# Blank_48LQFP_header.net
KiCad netlist of a schematic drawn in EAGLE
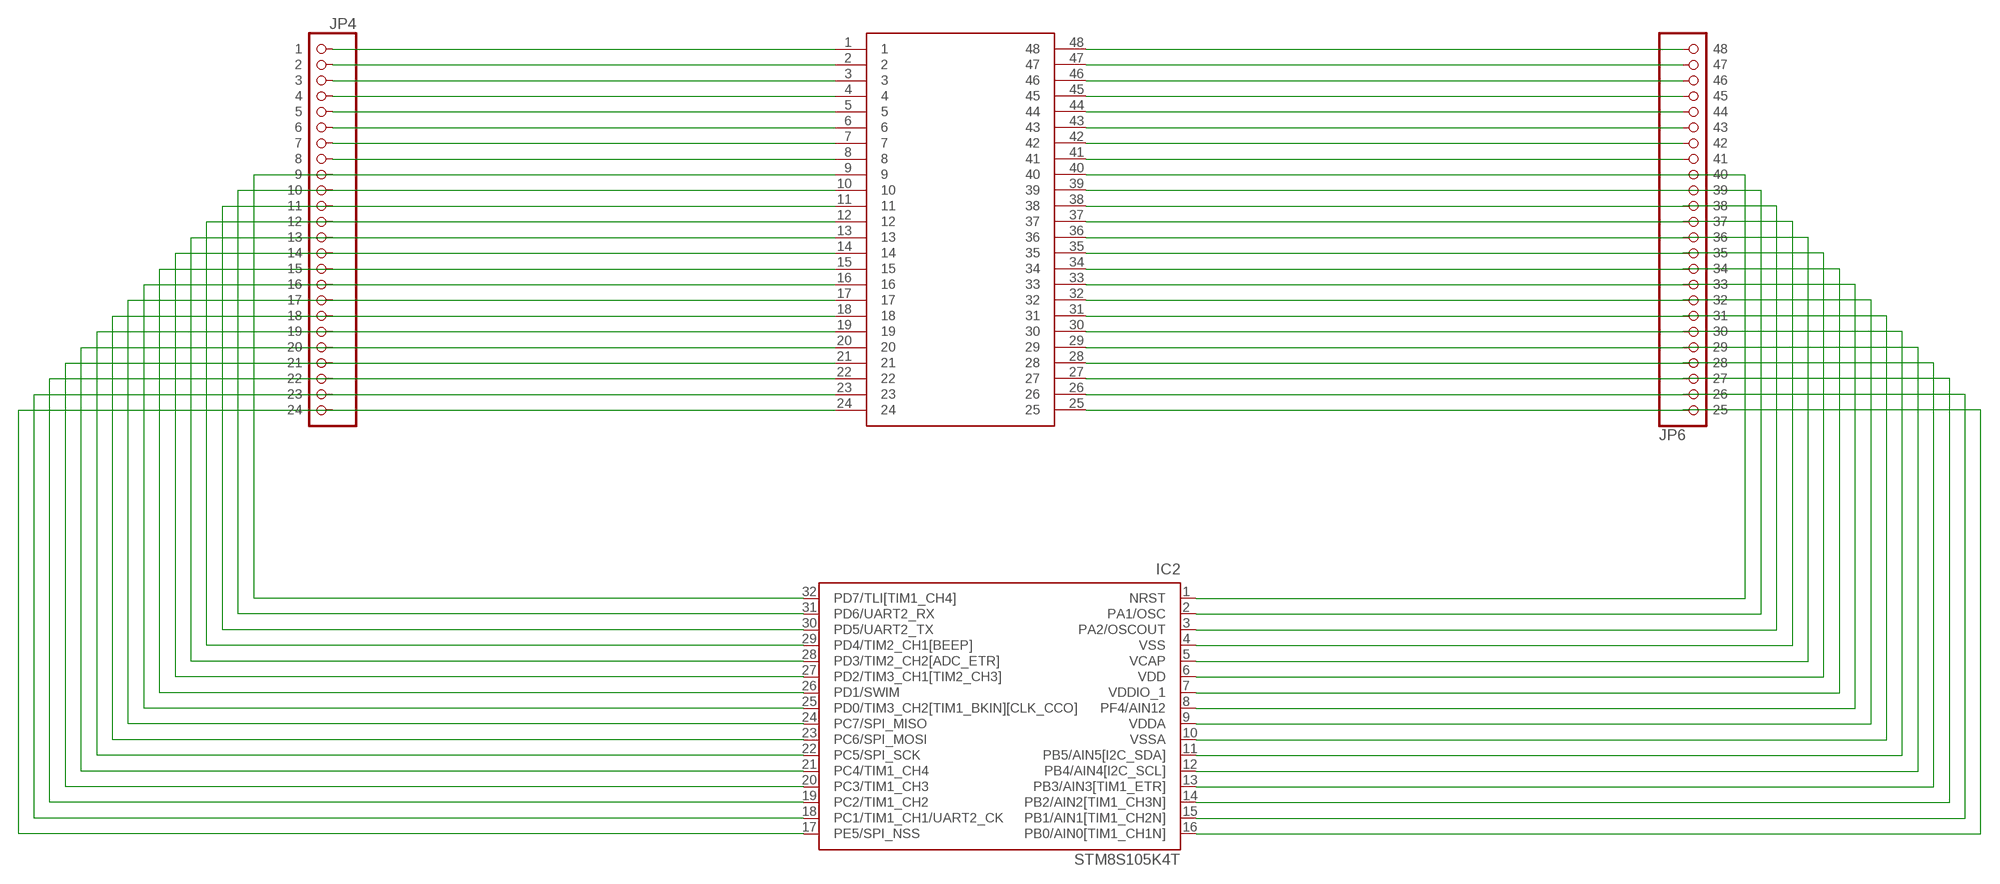
[diagram p0: schematic, sheet 1]

(export (version "E")
  (design (tool "Eeschema 10.0.6"))
  (components
    (comp (ref "IC2")
      (value "STM8S105K4T")
      (footprint "eagle-import:LQFP32-7X7")
      (fields (field (name "MPN") "STM8S105K4T6C"))
      (libsource (lib "eagle-import") (part "STM8S105KT4"))
    )
    (comp (ref "JP4")
      (value "PINHD-1X241X24_PINS_1_TO_24")
      (footprint "eagle-import:1X24")
      (libsource (lib "eagle-import") (part "PINHD-1X241X24_PINS_1_TO_24"))
    )
    (comp (ref "JP6")
      (value "PINHD-1X24-25TO48")
      (footprint "eagle-import:1X24")
      (libsource (lib "eagle-import") (part "PINHD-1X24-25TO48"))
    )
    (comp (ref "U$1")
      (value "GENERICLQFP48")
      (footprint "eagle-import:TQFP48")
      (libsource (lib "eagle-import") (part "GENERICLQFP48"))
    )
  )
  (nets
    (net (code "1") (name "Net-(IC2-NRST)") (class "Default")
      (node (ref "IC2") (pin "1") (pinfunction "NRST_1") (pintype "bidirectional"))
      (node (ref "JP6") (pin "16") (pinfunction "40_16") (pintype "passive"))
      (node (ref "U$1") (pin "40") (pinfunction "40_40") (pintype "bidirectional"))
    )
    (net (code "2") (name "Net-(IC2-PA1{slash}OSC)") (class "Default")
      (node (ref "IC2") (pin "2") (pinfunction "PA1/OSC_2") (pintype "bidirectional"))
      (node (ref "JP6") (pin "15") (pinfunction "39_15") (pintype "passive"))
      (node (ref "U$1") (pin "39") (pinfunction "39_39") (pintype "bidirectional"))
    )
    (net (code "3") (name "Net-(IC2-PA2{slash}OSCOUT)") (class "Default")
      (node (ref "IC2") (pin "3") (pinfunction "PA2/OSCOUT_3") (pintype "bidirectional"))
      (node (ref "JP6") (pin "14") (pinfunction "38_14") (pintype "passive"))
      (node (ref "U$1") (pin "38") (pinfunction "38_38") (pintype "bidirectional"))
    )
    (net (code "4") (name "Net-(IC2-PB0{slash}AIN0[TIM1_CH1N])") (class "Default")
      (node (ref "IC2") (pin "16") (pinfunction "PB0/AIN0[TIM1_CH1N]_16") (pintype "bidirectional"))
      (node (ref "JP6") (pin "1") (pinfunction "25_1") (pintype "passive"))
      (node (ref "U$1") (pin "25") (pinfunction "25_25") (pintype "bidirectional"))
    )
    (net (code "5") (name "Net-(IC2-PB1{slash}AIN1[TIM1_CH2N])") (class "Default")
      (node (ref "IC2") (pin "15") (pinfunction "PB1/AIN1[TIM1_CH2N]_15") (pintype "bidirectional"))
      (node (ref "JP6") (pin "2") (pinfunction "26_2") (pintype "passive"))
      (node (ref "U$1") (pin "26") (pinfunction "26_26") (pintype "bidirectional"))
    )
    (net (code "6") (name "Net-(IC2-PB2{slash}AIN2[TIM1_CH3N])") (class "Default")
      (node (ref "IC2") (pin "14") (pinfunction "PB2/AIN2[TIM1_CH3N]_14") (pintype "bidirectional"))
      (node (ref "JP6") (pin "3") (pinfunction "27_3") (pintype "passive"))
      (node (ref "U$1") (pin "27") (pinfunction "27_27") (pintype "bidirectional"))
    )
    (net (code "7") (name "Net-(IC2-PB3{slash}AIN3[TIM1_ETR])") (class "Default")
      (node (ref "IC2") (pin "13") (pinfunction "PB3/AIN3[TIM1_ETR]_13") (pintype "bidirectional"))
      (node (ref "JP6") (pin "4") (pinfunction "28_4") (pintype "passive"))
      (node (ref "U$1") (pin "28") (pinfunction "28_28") (pintype "bidirectional"))
    )
    (net (code "8") (name "Net-(IC2-PB4{slash}AIN4[I2C_SCL])") (class "Default")
      (node (ref "IC2") (pin "12") (pinfunction "PB4/AIN4[I2C_SCL]_12") (pintype "bidirectional"))
      (node (ref "JP6") (pin "5") (pinfunction "29_5") (pintype "passive"))
      (node (ref "U$1") (pin "29") (pinfunction "29_29") (pintype "bidirectional"))
    )
    (net (code "9") (name "Net-(IC2-PB5{slash}AIN5[I2C_SDA])") (class "Default")
      (node (ref "IC2") (pin "11") (pinfunction "PB5/AIN5[I2C_SDA]_11") (pintype "bidirectional"))
      (node (ref "JP6") (pin "6") (pinfunction "30_6") (pintype "passive"))
      (node (ref "U$1") (pin "30") (pinfunction "30_30") (pintype "bidirectional"))
    )
    (net (code "10") (name "Net-(IC2-PC1{slash}TIM1_CH1{slash}UART2_CK)") (class "Default")
      (node (ref "IC2") (pin "18") (pinfunction "PC1/TIM1_CH1/UART2_CK_18") (pintype "bidirectional"))
      (node (ref "JP4") (pin "23") (pinfunction "23_23") (pintype "passive"))
      (node (ref "U$1") (pin "23") (pinfunction "23_23") (pintype "bidirectional"))
    )
    (net (code "11") (name "Net-(IC2-PC2{slash}TIM1_CH2)") (class "Default")
      (node (ref "IC2") (pin "19") (pinfunction "PC2/TIM1_CH2_19") (pintype "bidirectional"))
      (node (ref "JP4") (pin "22") (pinfunction "22_22") (pintype "passive"))
      (node (ref "U$1") (pin "22") (pinfunction "22_22") (pintype "bidirectional"))
    )
    (net (code "12") (name "Net-(IC2-PC3{slash}TIM1_CH3)") (class "Default")
      (node (ref "IC2") (pin "20") (pinfunction "PC3/TIM1_CH3_20") (pintype "bidirectional"))
      (node (ref "JP4") (pin "21") (pinfunction "21_21") (pintype "passive"))
      (node (ref "U$1") (pin "21") (pinfunction "21_21") (pintype "bidirectional"))
    )
    (net (code "13") (name "Net-(IC2-PC4{slash}TIM1_CH4)") (class "Default")
      (node (ref "IC2") (pin "21") (pinfunction "PC4/TIM1_CH4_21") (pintype "bidirectional"))
      (node (ref "JP4") (pin "20") (pinfunction "20_20") (pintype "passive"))
      (node (ref "U$1") (pin "20") (pinfunction "20_20") (pintype "bidirectional"))
    )
    (net (code "14") (name "Net-(IC2-PC5{slash}SPI_SCK)") (class "Default")
      (node (ref "IC2") (pin "22") (pinfunction "PC5/SPI_SCK_22") (pintype "bidirectional"))
      (node (ref "JP4") (pin "19") (pinfunction "19_19") (pintype "passive"))
      (node (ref "U$1") (pin "19") (pinfunction "19_19") (pintype "bidirectional"))
    )
    (net (code "15") (name "Net-(IC2-PC6{slash}SPI_MOSI)") (class "Default")
      (node (ref "IC2") (pin "23") (pinfunction "PC6/SPI_MOSI_23") (pintype "bidirectional"))
      (node (ref "JP4") (pin "18") (pinfunction "18_18") (pintype "passive"))
      (node (ref "U$1") (pin "18") (pinfunction "18_18") (pintype "bidirectional"))
    )
    (net (code "16") (name "Net-(IC2-PC7{slash}SPI_MISO)") (class "Default")
      (node (ref "IC2") (pin "24") (pinfunction "PC7/SPI_MISO_24") (pintype "bidirectional"))
      (node (ref "JP4") (pin "17") (pinfunction "17_17") (pintype "passive"))
      (node (ref "U$1") (pin "17") (pinfunction "17_17") (pintype "bidirectional"))
    )
    (net (code "17") (name "Net-(IC2-PD0{slash}TIM3_CH2[TIM1_BKIN][CLK_CCO])") (class "Default")
      (node (ref "IC2") (pin "25") (pinfunction "PD0/TIM3_CH2[TIM1_BKIN][CLK_CCO]_25") (pintype "bidirectional"))
      (node (ref "JP4") (pin "16") (pinfunction "16_16") (pintype "passive"))
      (node (ref "U$1") (pin "16") (pinfunction "16_16") (pintype "bidirectional"))
    )
    (net (code "18") (name "Net-(IC2-PD1{slash}SWIM)") (class "Default")
      (node (ref "IC2") (pin "26") (pinfunction "PD1/SWIM_26") (pintype "bidirectional"))
      (node (ref "JP4") (pin "15") (pinfunction "15_15") (pintype "passive"))
      (node (ref "U$1") (pin "15") (pinfunction "15_15") (pintype "bidirectional"))
    )
    (net (code "19") (name "Net-(IC2-PD2{slash}TIM3_CH1[TIM2_CH3])") (class "Default")
      (node (ref "IC2") (pin "27") (pinfunction "PD2/TIM3_CH1[TIM2_CH3]_27") (pintype "bidirectional"))
      (node (ref "JP4") (pin "14") (pinfunction "14_14") (pintype "passive"))
      (node (ref "U$1") (pin "14") (pinfunction "14_14") (pintype "bidirectional"))
    )
    (net (code "20") (name "Net-(IC2-PD3{slash}TIM2_CH2[ADC_ETR])") (class "Default")
      (node (ref "IC2") (pin "28") (pinfunction "PD3/TIM2_CH2[ADC_ETR]_28") (pintype "bidirectional"))
      (node (ref "JP4") (pin "13") (pinfunction "13_13") (pintype "passive"))
      (node (ref "U$1") (pin "13") (pinfunction "13_13") (pintype "bidirectional"))
    )
    (net (code "21") (name "Net-(IC2-PD4{slash}TIM2_CH1[BEEP])") (class "Default")
      (node (ref "IC2") (pin "29") (pinfunction "PD4/TIM2_CH1[BEEP]_29") (pintype "bidirectional"))
      (node (ref "JP4") (pin "12") (pinfunction "12_12") (pintype "passive"))
      (node (ref "U$1") (pin "12") (pinfunction "12_12") (pintype "bidirectional"))
    )
    (net (code "22") (name "Net-(IC2-PD5{slash}UART2_TX)") (class "Default")
      (node (ref "IC2") (pin "30") (pinfunction "PD5/UART2_TX_30") (pintype "bidirectional"))
      (node (ref "JP4") (pin "11") (pinfunction "11_11") (pintype "passive"))
      (node (ref "U$1") (pin "11") (pinfunction "11_11") (pintype "bidirectional"))
    )
    (net (code "23") (name "Net-(IC2-PD6{slash}UART2_RX)") (class "Default")
      (node (ref "IC2") (pin "31") (pinfunction "PD6/UART2_RX_31") (pintype "bidirectional"))
      (node (ref "JP4") (pin "10") (pinfunction "10_10") (pintype "passive"))
      (node (ref "U$1") (pin "10") (pinfunction "10_10") (pintype "bidirectional"))
    )
    (net (code "24") (name "Net-(IC2-PD7{slash}TLI[TIM1_CH4])") (class "Default")
      (node (ref "IC2") (pin "32") (pinfunction "PD7/TLI[TIM1_CH4]_32") (pintype "bidirectional"))
      (node (ref "JP4") (pin "9") (pinfunction "9_9") (pintype "passive"))
      (node (ref "U$1") (pin "9") (pinfunction "9_9") (pintype "bidirectional"))
    )
    (net (code "25") (name "Net-(IC2-PE5{slash}SPI_NSS)") (class "Default")
      (node (ref "IC2") (pin "17") (pinfunction "PE5/SPI_NSS_17") (pintype "bidirectional"))
      (node (ref "JP4") (pin "24") (pinfunction "24_24") (pintype "passive"))
      (node (ref "U$1") (pin "24") (pinfunction "24_24") (pintype "bidirectional"))
    )
    (net (code "26") (name "Net-(IC2-PF4{slash}AIN12)") (class "Default")
      (node (ref "IC2") (pin "8") (pinfunction "PF4/AIN12_8") (pintype "bidirectional"))
      (node (ref "JP6") (pin "9") (pinfunction "33_9") (pintype "passive"))
      (node (ref "U$1") (pin "33") (pinfunction "33_33") (pintype "bidirectional"))
    )
    (net (code "27") (name "Net-(IC2-VCAP)") (class "Default")
      (node (ref "IC2") (pin "5") (pinfunction "VCAP_5") (pintype "power_in"))
      (node (ref "JP6") (pin "12") (pinfunction "36_12") (pintype "passive"))
      (node (ref "U$1") (pin "36") (pinfunction "36_36") (pintype "bidirectional"))
    )
    (net (code "28") (name "Net-(IC2-VDD)") (class "Default")
      (node (ref "IC2") (pin "6") (pinfunction "VDD_6") (pintype "power_in"))
      (node (ref "JP6") (pin "11") (pinfunction "35_11") (pintype "passive"))
      (node (ref "U$1") (pin "35") (pinfunction "35_35") (pintype "bidirectional"))
    )
    (net (code "29") (name "Net-(IC2-VDDA)") (class "Default")
      (node (ref "IC2") (pin "9") (pinfunction "VDDA_9") (pintype "power_in"))
      (node (ref "JP6") (pin "8") (pinfunction "32_8") (pintype "passive"))
      (node (ref "U$1") (pin "32") (pinfunction "32_32") (pintype "bidirectional"))
    )
    (net (code "30") (name "Net-(IC2-VDDIO_1)") (class "Default")
      (node (ref "IC2") (pin "7") (pinfunction "VDDIO_1_7") (pintype "power_in"))
      (node (ref "JP6") (pin "10") (pinfunction "34_10") (pintype "passive"))
      (node (ref "U$1") (pin "34") (pinfunction "34_34") (pintype "bidirectional"))
    )
    (net (code "31") (name "Net-(IC2-VSS)") (class "Default")
      (node (ref "IC2") (pin "4") (pinfunction "VSS_4") (pintype "power_in"))
      (node (ref "JP6") (pin "13") (pinfunction "37_13") (pintype "passive"))
      (node (ref "U$1") (pin "37") (pinfunction "37_37") (pintype "bidirectional"))
    )
    (net (code "32") (name "Net-(IC2-VSSA)") (class "Default")
      (node (ref "IC2") (pin "10") (pinfunction "VSSA_10") (pintype "power_in"))
      (node (ref "JP6") (pin "7") (pinfunction "31_7") (pintype "passive"))
      (node (ref "U$1") (pin "31") (pinfunction "31_31") (pintype "bidirectional"))
    )
    (net (code "33") (name "Net-(JP4-Pad1)") (class "Default")
      (node (ref "JP4") (pin "1") (pinfunction "1_1") (pintype "passive"))
      (node (ref "U$1") (pin "1") (pinfunction "1_1") (pintype "bidirectional"))
    )
    (net (code "34") (name "Net-(JP4-Pad2)") (class "Default")
      (node (ref "JP4") (pin "2") (pinfunction "2_2") (pintype "passive"))
      (node (ref "U$1") (pin "2") (pinfunction "2_2") (pintype "bidirectional"))
    )
    (net (code "35") (name "Net-(JP4-Pad3)") (class "Default")
      (node (ref "JP4") (pin "3") (pinfunction "3_3") (pintype "passive"))
      (node (ref "U$1") (pin "3") (pinfunction "3_3") (pintype "bidirectional"))
    )
    (net (code "36") (name "Net-(JP4-Pad4)") (class "Default")
      (node (ref "JP4") (pin "4") (pinfunction "4_4") (pintype "passive"))
      (node (ref "U$1") (pin "4") (pinfunction "4_4") (pintype "bidirectional"))
    )
    (net (code "37") (name "Net-(JP4-Pad5)") (class "Default")
      (node (ref "JP4") (pin "5") (pinfunction "5_5") (pintype "passive"))
      (node (ref "U$1") (pin "5") (pinfunction "5_5") (pintype "bidirectional"))
    )
    (net (code "38") (name "Net-(JP4-Pad6)") (class "Default")
      (node (ref "JP4") (pin "6") (pinfunction "6_6") (pintype "passive"))
      (node (ref "U$1") (pin "6") (pinfunction "6_6") (pintype "bidirectional"))
    )
    (net (code "39") (name "Net-(JP4-Pad7)") (class "Default")
      (node (ref "JP4") (pin "7") (pinfunction "7_7") (pintype "passive"))
      (node (ref "U$1") (pin "7") (pinfunction "7_7") (pintype "bidirectional"))
    )
    (net (code "40") (name "Net-(JP4-Pad8)") (class "Default")
      (node (ref "JP4") (pin "8") (pinfunction "8_8") (pintype "passive"))
      (node (ref "U$1") (pin "8") (pinfunction "8_8") (pintype "bidirectional"))
    )
    (net (code "41") (name "Net-(JP6-41)") (class "Default")
      (node (ref "JP6") (pin "17") (pinfunction "41_17") (pintype "passive"))
      (node (ref "U$1") (pin "41") (pinfunction "41_41") (pintype "bidirectional"))
    )
    (net (code "42") (name "Net-(JP6-42)") (class "Default")
      (node (ref "JP6") (pin "18") (pinfunction "42_18") (pintype "passive"))
      (node (ref "U$1") (pin "42") (pinfunction "42_42") (pintype "bidirectional"))
    )
    (net (code "43") (name "Net-(JP6-43)") (class "Default")
      (node (ref "JP6") (pin "19") (pinfunction "43_19") (pintype "passive"))
      (node (ref "U$1") (pin "43") (pinfunction "43_43") (pintype "bidirectional"))
    )
    (net (code "44") (name "Net-(JP6-44)") (class "Default")
      (node (ref "JP6") (pin "20") (pinfunction "44_20") (pintype "passive"))
      (node (ref "U$1") (pin "44") (pinfunction "44_44") (pintype "bidirectional"))
    )
    (net (code "45") (name "Net-(JP6-45)") (class "Default")
      (node (ref "JP6") (pin "21") (pinfunction "45_21") (pintype "passive"))
      (node (ref "U$1") (pin "45") (pinfunction "45_45") (pintype "bidirectional"))
    )
    (net (code "46") (name "Net-(JP6-46)") (class "Default")
      (node (ref "JP6") (pin "22") (pinfunction "46_22") (pintype "passive"))
      (node (ref "U$1") (pin "46") (pinfunction "46_46") (pintype "bidirectional"))
    )
    (net (code "47") (name "Net-(JP6-47)") (class "Default")
      (node (ref "JP6") (pin "23") (pinfunction "47_23") (pintype "passive"))
      (node (ref "U$1") (pin "47") (pinfunction "47_47") (pintype "bidirectional"))
    )
    (net (code "48") (name "Net-(JP6-48)") (class "Default")
      (node (ref "JP6") (pin "24") (pinfunction "48_24") (pintype "passive"))
      (node (ref "U$1") (pin "48") (pinfunction "48_48") (pintype "bidirectional"))
    )
  )
)
